# Power.net
KiCad netlist of a schematic drawn in Altium Designer
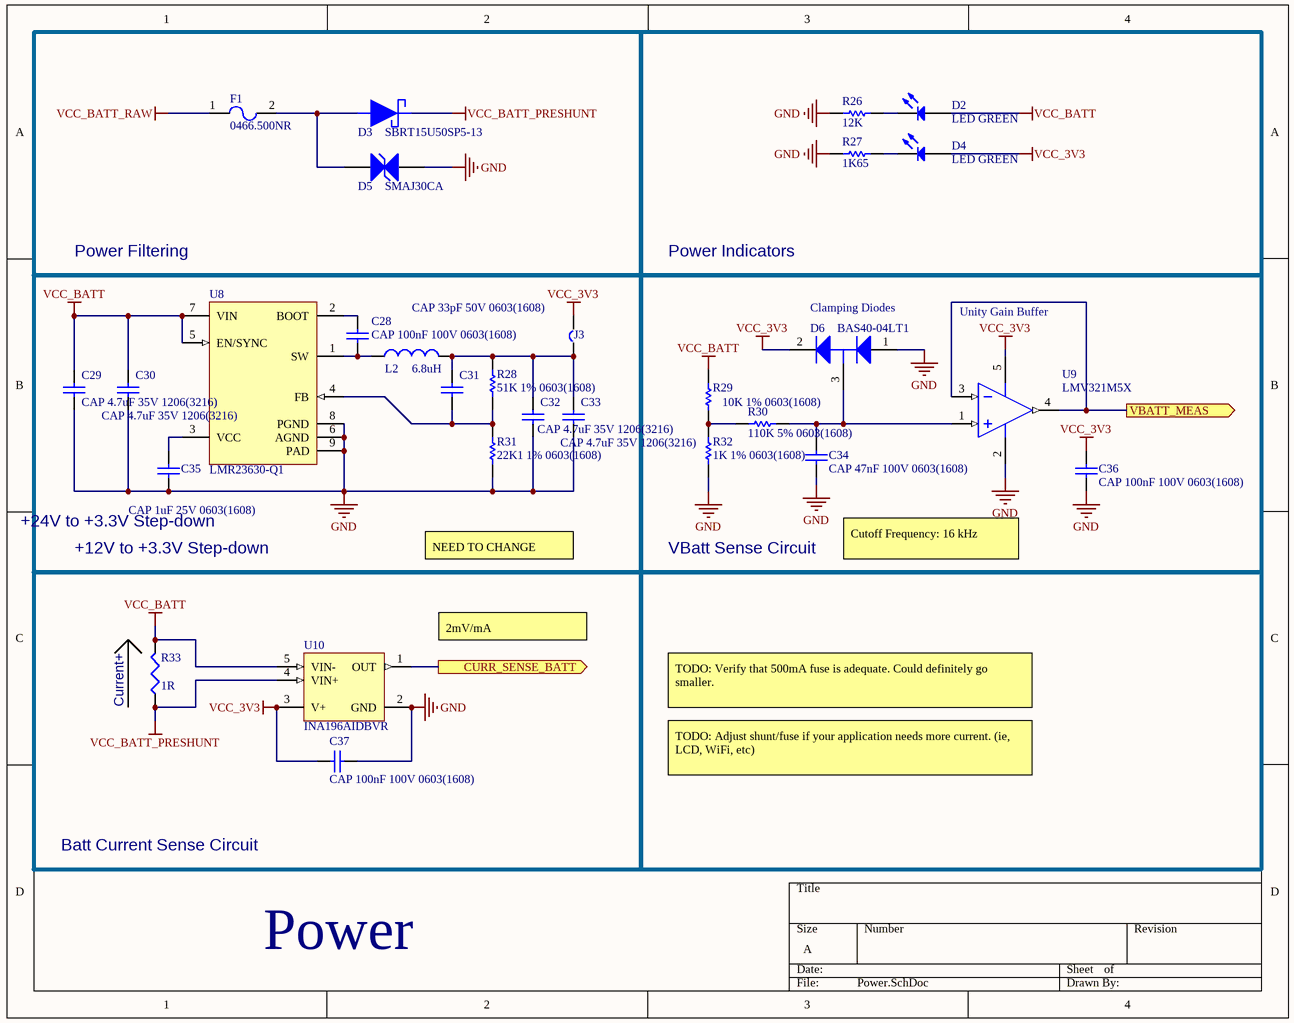
[diagram p0: Power.SchDoc]

(export (version "E")
  (design (tool "Eeschema 10.0.6"))
  (components
    (comp (ref "C28")
      (value "CAP 100nF 100V 0603(1608)")
      (footprint "CAPC0603(1608)100_L")
      (description "CAP 100nF 100V ±10% 0603 (1608 Metric) Thickness 1mm SMD")
      (fields (field (name "TOLERANCE") "Â±10%"))
      (libsource (lib "Altium Content Vault") (part "CAP"))
    )
    (comp (ref "C29")
      (value "CAP 4.7uF 35V 1206(3216)")
      (footprint "CAPC1206(3216)190_L")
      (description "CAP 4.7uF 35V ±10% 1206 (3216 Metric) Thickness 1.9mm SMD")
      (fields (field (name "TOLERANCE") "Â±10%"))
      (libsource (lib "Altium Content Vault") (part "CAP"))
    )
    (comp (ref "C30")
      (value "CAP 4.7uF 35V 1206(3216)")
      (footprint "CAPC1206(3216)190_L")
      (description "CAP 4.7uF 35V ±10% 1206 (3216 Metric) Thickness 1.9mm SMD")
      (fields (field (name "TOLERANCE") "Â±10%"))
      (libsource (lib "Altium Content Vault") (part "CAP"))
    )
    (comp (ref "C31")
      (value "CAP 33pF 50V 0603(1608)")
      (footprint "CAPC0603(1608)100_M")
      (description "CAP 33pF 50V ±5% 0603 (1608 Metric) Thickness 1mm SMD")
      (fields (field (name "TOLERANCE") "Â±5%"))
      (libsource (lib "Altium Content Vault") (part "CAP"))
    )
    (comp (ref "C32")
      (value "CAP 4.7uF 35V 1206(3216)")
      (footprint "CAPC1206(3216)190_L")
      (description "CAP 4.7uF 35V ±10% 1206 (3216 Metric) Thickness 1.9mm SMD")
      (fields (field (name "TOLERANCE") "Â±10%"))
      (libsource (lib "Altium Content Vault") (part "CAP"))
    )
    (comp (ref "C33")
      (value "CAP 4.7uF 35V 1206(3216)")
      (footprint "CAPC1206(3216)190_L")
      (description "CAP 4.7uF 35V ±10% 1206 (3216 Metric) Thickness 1.9mm SMD")
      (fields (field (name "TOLERANCE") "Â±10%"))
      (libsource (lib "Altium Content Vault") (part "CAP"))
    )
    (comp (ref "C34")
      (value "CAP 47nF 100V 0603(1608)")
      (footprint "CAPC0603(1608)100_N")
      (description "CAP 47nF 100V ±10% 0603 (1608 Metric) Thickness 1mm SMD")
      (fields (field (name "TOLERANCE") "Â±10%"))
      (libsource (lib "Altium Content Vault") (part "CAP"))
    )
    (comp (ref "C35")
      (value "CAP 1uF 25V 0603(1608)")
      (footprint "CAPC0603(1608)100_L")
      (description "CAP 1uF 25V ±10% 0603 (1608 Metric) Thickness 1mm SMD")
      (fields (field (name "TOLERANCE") "Â±10%"))
      (libsource (lib "Altium Content Vault") (part "CAP"))
    )
    (comp (ref "C36")
      (value "CAP 100nF 100V 0603(1608)")
      (footprint "CAPC0603(1608)100_L")
      (description "CAP 100nF 100V ±10% 0603 (1608 Metric) Thickness 1mm SMD")
      (fields (field (name "TOLERANCE") "Â±10%"))
      (libsource (lib "Altium Content Vault") (part "CAP"))
    )
    (comp (ref "C37")
      (value "CAP 100nF 100V 0603(1608)")
      (footprint "CAPC0603(1608)100_L")
      (description "CAP 100nF 100V ±10% 0603 (1608 Metric) Thickness 1mm SMD")
      (fields (field (name "TOLERANCE") "Â±10%"))
      (libsource (lib "Altium Content Vault") (part "CAP"))
    )
    (comp (ref "D2")
      (value "LED GREEN")
      (footprint "LED_0805")
      (description "led")
      (fields
        (field (name "MANUFACTURER") "Lite-On Inc.")
        (field (name "MANUFACTURER PART NUMBER") "LTST-C171KGKT")
      )
      (libsource (lib "CMR_Miscellaneous_Devices") (part "LED0"))
    )
    (comp (ref "D3")
      (value "SBRT15U50SP5-13")
      (footprint "SBRT15U50SP5-13")
      (libsource (lib "CMR_Miscellaneous_Devices") (part "SBRT15U50SP5-13"))
    )
    (comp (ref "D4")
      (value "LED GREEN")
      (footprint "LED_0805")
      (description "led")
      (fields
        (field (name "MANUFACTURER") "Lite-On Inc.")
        (field (name "MANUFACTURER PART NUMBER") "LTST-C171KGKT")
      )
      (libsource (lib "CMR_Miscellaneous_Devices") (part "LED0"))
    )
    (comp (ref "D5")
      (value "SMAJ30CA")
      (footprint "LFUS-DO-214AC-A-2_V")
      (description "Transient Voltage Suppression Diode, 30 V, -65 to 150 degC, 2-Pin SMD, RoHS, Tape and Reel")
      (fields (field (name "MANUFACTURER") "Littelfuse-Inc."))
      (libsource (lib "Altium Content Vault") (part "DZEN-AA-2"))
    )
    (comp (ref "D6")
      (value "BAS40-04LT1")
      (footprint "ONSC-SOT-23-3-318-08_V")
      (description "Dual Series Schottky Barrier Diodes, 3-Pin SOT-23, Tape and Reel")
      (fields (field (name "MANUFACTURER") "On Semiconductor"))
      (libsource (lib "Altium Content Vault") (part "ONSC-D-A1K2C3-3"))
    )
    (comp (ref "F1")
      (value "0466.500NR")
      (footprint "0466.500NR")
      (description "FUSE BOARD MOUNT 500MA 63VAC/VDC")
      (libsource (lib "CMR_Miscellaneous_Devices") (part "0466.500NR"))
    )
    (comp (ref "J3")
      (value "(Open)")
      (footprint "Solder Jumper")
      (description "Jumper")
      (libsource (lib "CMR_PCB_Components") (part "Jumper"))
    )
    (comp (ref "L2")
      (value "6.8uH")
      (footprint "BOURNS SRP5030T")
      (fields
        (field (name "MANUFACTURER") "Bourns Inc.")
        (field (name "MANUFACTURER PART NUMBER") "SRP5030TA-6R8M")
        (field (name "TOLERANCE") "±20%")
      )
      (libsource (lib "CMR_Miscellaneous_Devices") (part "SRP5030TA"))
    )
    (comp (ref "R26")
      (value "12K")
      (footprint "RESC0603(1608)_N")
      (description "100R 0.1W 5% 0603 (1608 Metric)  SMD")
      (fields (field (name "TOLERANCE") "5 %") (field (name "POWER") "0.1 W"))
      (libsource (lib "Altium Content Vault") (part "CMP-1012-00050-1"))
    )
    (comp (ref "R27")
      (value "1K65")
      (footprint "RESC0603(1608)_N")
      (description "100R 0.1W 5% 0603 (1608 Metric)  SMD")
      (fields (field (name "TOLERANCE") "5 %") (field (name "POWER") "0.1 W"))
      (libsource (lib "Altium Content Vault") (part "CMP-1012-00050-1"))
    )
    (comp (ref "R28")
      (value "51K 1% 0603(1608)")
      (footprint "RESC0603(1608)_N")
      (description "51K 0.1W 1% 0603 (1608 Metric)  SMD")
      (fields (field (name "TOLERANCE") "1 %") (field (name "POWER") "0.1 W"))
      (libsource (lib "Altium Content Vault") (part "RES"))
    )
    (comp (ref "R29")
      (value "10K 1% 0603(1608)")
      (footprint "RESC0603(1608)_N")
      (description "10K 0.1W 1% 0603 (1608 Metric)  SMD")
      (fields (field (name "POWER") "0.1 W") (field (name "TOLERANCE") "1 %"))
      (libsource (lib "Altium Content Vault") (part "RES"))
    )
    (comp (ref "R30")
      (value "110K 5% 0603(1608)")
      (footprint "RESC0603(1608)_M")
      (description "110K 0.1W 5% 0603 (1608 Metric)  SMD")
      (fields (field (name "TOLERANCE") "5 %") (field (name "POWER") "0.1 W"))
      (libsource (lib "Altium Content Vault") (part "RES"))
    )
    (comp (ref "R31")
      (value "22K1 1% 0603(1608)")
      (footprint "RESC0603(1608)_N")
      (description "22K1 0.1W 1% 0603 (1608 Metric)  SMD")
      (fields (field (name "TOLERANCE") "1 %") (field (name "POWER") "0.1 W"))
      (libsource (lib "Altium Content Vault") (part "RES"))
    )
    (comp (ref "R32")
      (value "1K 1% 0603(1608)")
      (footprint "RESC0603(1608)_M")
      (description "1K 0.1W 1% 0603 (1608 Metric)  SMD")
      (fields (field (name "TOLERANCE") "1 %") (field (name "POWER") "0.1 W"))
      (libsource (lib "Altium Content Vault") (part "RES"))
    )
    (comp (ref "R33")
      (value "1R")
      (footprint "C1206")
      (description "Resistor")
      (fields (field (name "TOLERANCE") "1%") (field (name "PUBLISHER") "Altium Limited"))
      (libsource (lib "Miscellaneous Devices") (part "Res3"))
    )
    (comp (ref "U8")
      (value "LMR23630-Q1")
      (footprint "DDA0008E_N")
      (fields
        (field (name "MANUFACTURER") "Texas Instruments")
        (field (name "MANUFACTURER PART NUMBER") "LMR23630AFQDDARQ1")
      )
      (libsource (lib "CMR_Miscellaneous_Devices") (part "LMR23630-Q1"))
    )
    (comp (ref "U9")
      (value "LMV321M5X")
      (footprint "DBV0005A_N")
      (description "General Purpose, Low Voltage, Rail-to-Rail Output Operational Amplifiers, 5-pin SOT-23")
      (fields (field (name "MANUFACTURER") "Texas Instruments"))
      (libsource (lib "Altium Content Vault") (part "AMP-OPA-LMV551-5"))
    )
    (comp (ref "U10")
      (value "INA196AIDBVR")
      (footprint "DBV0005A_L")
      (fields (field (name "MANUFACTURER") "Texas Instruments"))
      (libsource (lib "Altium Content Vault") (part "TI-INA196_197_198DBV5"))
    )
  )
  (nets
    (net (code "1") (name "/CURR_SENSE_BATT") (class "Default")
      (node (ref "U10") (pin "1") (pinfunction "OUT_1") (pintype "output"))
    )
    (net (code "2") (name "/VBATT_MEAS") (class "Default")
      (node (ref "U9") (pin "3") (pinfunction "IN-_3") (pintype "input"))
      (node (ref "U9") (pin "4") (pinfunction "OUT_4") (pintype "output"))
    )
    (net (code "3") (name "GND") (class "Default")
      (node (ref "C29") (pin "1") (pinfunction "1_1") (pintype "passive"))
      (node (ref "C30") (pin "1") (pinfunction "1_1") (pintype "passive"))
      (node (ref "C32") (pin "1") (pinfunction "1_1") (pintype "passive"))
      (node (ref "C33") (pin "1") (pinfunction "1_1") (pintype "passive"))
      (node (ref "C34") (pin "1") (pinfunction "1_1") (pintype "passive"))
      (node (ref "C35") (pin "1") (pinfunction "1_1") (pintype "passive"))
      (node (ref "C36") (pin "2") (pinfunction "2_2") (pintype "passive"))
      (node (ref "C37") (pin "1") (pinfunction "1_1") (pintype "passive"))
      (node (ref "D5") (pin "2") (pinfunction "A_2") (pintype "passive"))
      (node (ref "D6") (pin "1") (pinfunction "A_1") (pintype "passive"))
      (node (ref "R26") (pin "1") (pinfunction "1_1") (pintype "passive"))
      (node (ref "R27") (pin "1") (pinfunction "1_1") (pintype "passive"))
      (node (ref "R31") (pin "1") (pinfunction "1_1") (pintype "passive"))
      (node (ref "R32") (pin "1") (pinfunction "1_1") (pintype "passive"))
      (node (ref "U10") (pin "2") (pinfunction "GND_2") (pintype "power_in"))
      (node (ref "U8") (pin "6") (pinfunction "AGND_6") (pintype "passive"))
      (node (ref "U8") (pin "8") (pinfunction "PGND_8") (pintype "passive"))
      (node (ref "U8") (pin "9") (pinfunction "PAD_9") (pintype "passive"))
      (node (ref "U9") (pin "2") (pinfunction "V-_2") (pintype "power_in"))
    )
    (net (code "4") (name "Net-(C31-Pad2)") (class "Default")
      (node (ref "C31") (pin "2") (pinfunction "2_2") (pintype "passive"))
      (node (ref "C32") (pin "2") (pinfunction "2_2") (pintype "passive"))
      (node (ref "C33") (pin "2") (pinfunction "2_2") (pintype "passive"))
      (node (ref "J3") (pin "1") (pinfunction "1_1") (pintype "passive"))
      (node (ref "L2") (pin "2") (pinfunction "2_2") (pintype "passive"))
      (node (ref "R28") (pin "2") (pinfunction "2_2") (pintype "passive"))
    )
    (net (code "5") (name "Net-(D2-K)") (class "Default")
      (node (ref "D2") (pin "1") (pinfunction "K_1") (pintype "passive"))
      (node (ref "R26") (pin "2") (pinfunction "2_2") (pintype "passive"))
    )
    (net (code "6") (name "Net-(D3-Pad1)") (class "Default")
      (node (ref "D3") (pin "1") (pinfunction "1_1") (pintype "passive"))
      (node (ref "D5") (pin "1") (pinfunction "A_1") (pintype "passive"))
      (node (ref "F1") (pin "2") (pinfunction "2_2") (pintype "passive"))
    )
    (net (code "7") (name "Net-(D4-K)") (class "Default")
      (node (ref "D4") (pin "1") (pinfunction "K_1") (pintype "passive"))
      (node (ref "R27") (pin "2") (pinfunction "2_2") (pintype "passive"))
    )
    (net (code "8") (name "Net-(D6-K{slash}A)") (class "Default")
      (node (ref "C34") (pin "2") (pinfunction "2_2") (pintype "passive"))
      (node (ref "D6") (pin "3") (pinfunction "K/A_3") (pintype "passive"))
      (node (ref "R30") (pin "2") (pinfunction "2_2") (pintype "passive"))
      (node (ref "U9") (pin "1") (pinfunction "IN+_1") (pintype "input"))
    )
    (net (code "9") (name "Net-(R29-Pad1)") (class "Default")
      (node (ref "R29") (pin "1") (pinfunction "1_1") (pintype "passive"))
      (node (ref "R30") (pin "1") (pinfunction "1_1") (pintype "passive"))
      (node (ref "R32") (pin "2") (pinfunction "2_2") (pintype "passive"))
    )
    (net (code "10") (name "Net-(U8-BOOT)") (class "Default")
      (node (ref "C28") (pin "2") (pinfunction "2_2") (pintype "passive"))
      (node (ref "U8") (pin "2") (pinfunction "BOOT_2") (pintype "passive"))
    )
    (net (code "11") (name "Net-(U8-FB)") (class "Default")
      (node (ref "C31") (pin "1") (pinfunction "1_1") (pintype "passive"))
      (node (ref "R28") (pin "1") (pinfunction "1_1") (pintype "passive"))
      (node (ref "R31") (pin "2") (pinfunction "2_2") (pintype "passive"))
      (node (ref "U8") (pin "4") (pinfunction "FB_4") (pintype "input"))
    )
    (net (code "12") (name "Net-(U8-SW)") (class "Default")
      (node (ref "C28") (pin "1") (pinfunction "1_1") (pintype "passive"))
      (node (ref "L2") (pin "1") (pinfunction "1_1") (pintype "passive"))
      (node (ref "U8") (pin "1") (pinfunction "SW_1") (pintype "passive"))
    )
    (net (code "13") (name "Net-(U8-VCC)") (class "Default")
      (node (ref "C35") (pin "2") (pinfunction "2_2") (pintype "passive"))
      (node (ref "U8") (pin "3") (pinfunction "VCC_3") (pintype "passive"))
    )
    (net (code "14") (name "VCC_3V3") (class "Default")
      (node (ref "C36") (pin "1") (pinfunction "1_1") (pintype "passive"))
      (node (ref "C37") (pin "2") (pinfunction "2_2") (pintype "passive"))
      (node (ref "D4") (pin "2") (pinfunction "A_2") (pintype "passive"))
      (node (ref "D6") (pin "2") (pinfunction "K_2") (pintype "passive"))
      (node (ref "J3") (pin "2") (pinfunction "2_2") (pintype "passive"))
      (node (ref "U10") (pin "3") (pinfunction "V+_3") (pintype "power_in"))
      (node (ref "U9") (pin "5") (pinfunction "V+_5") (pintype "power_in"))
    )
    (net (code "15") (name "VCC_BATT") (class "Default")
      (node (ref "C29") (pin "2") (pinfunction "2_2") (pintype "passive"))
      (node (ref "C30") (pin "2") (pinfunction "2_2") (pintype "passive"))
      (node (ref "D2") (pin "2") (pinfunction "A_2") (pintype "passive"))
      (node (ref "R29") (pin "2") (pinfunction "2_2") (pintype "passive"))
      (node (ref "R33") (pin "2") (pinfunction "2_2") (pintype "passive"))
      (node (ref "U10") (pin "5") (pinfunction "VIN-_5") (pintype "input"))
      (node (ref "U8") (pin "5") (pinfunction "EN/SYNC_5") (pintype "input"))
      (node (ref "U8") (pin "7") (pinfunction "VIN_7") (pintype "passive"))
    )
    (net (code "16") (name "VCC_BATT_PRESHUNT") (class "Default")
      (node (ref "D3") (pin "2") (pinfunction "2_2") (pintype "passive"))
      (node (ref "R33") (pin "1") (pinfunction "1_1") (pintype "passive"))
      (node (ref "U10") (pin "4") (pinfunction "VIN+_4") (pintype "input"))
    )
    (net (code "17") (name "VCC_BATT_RAW") (class "Default")
      (node (ref "F1") (pin "1") (pinfunction "1_1") (pintype "passive"))
    )
  )
)
